# 2025_06_24_cam.net
KiCad netlist of a schematic drawn in EasyEDA Pro
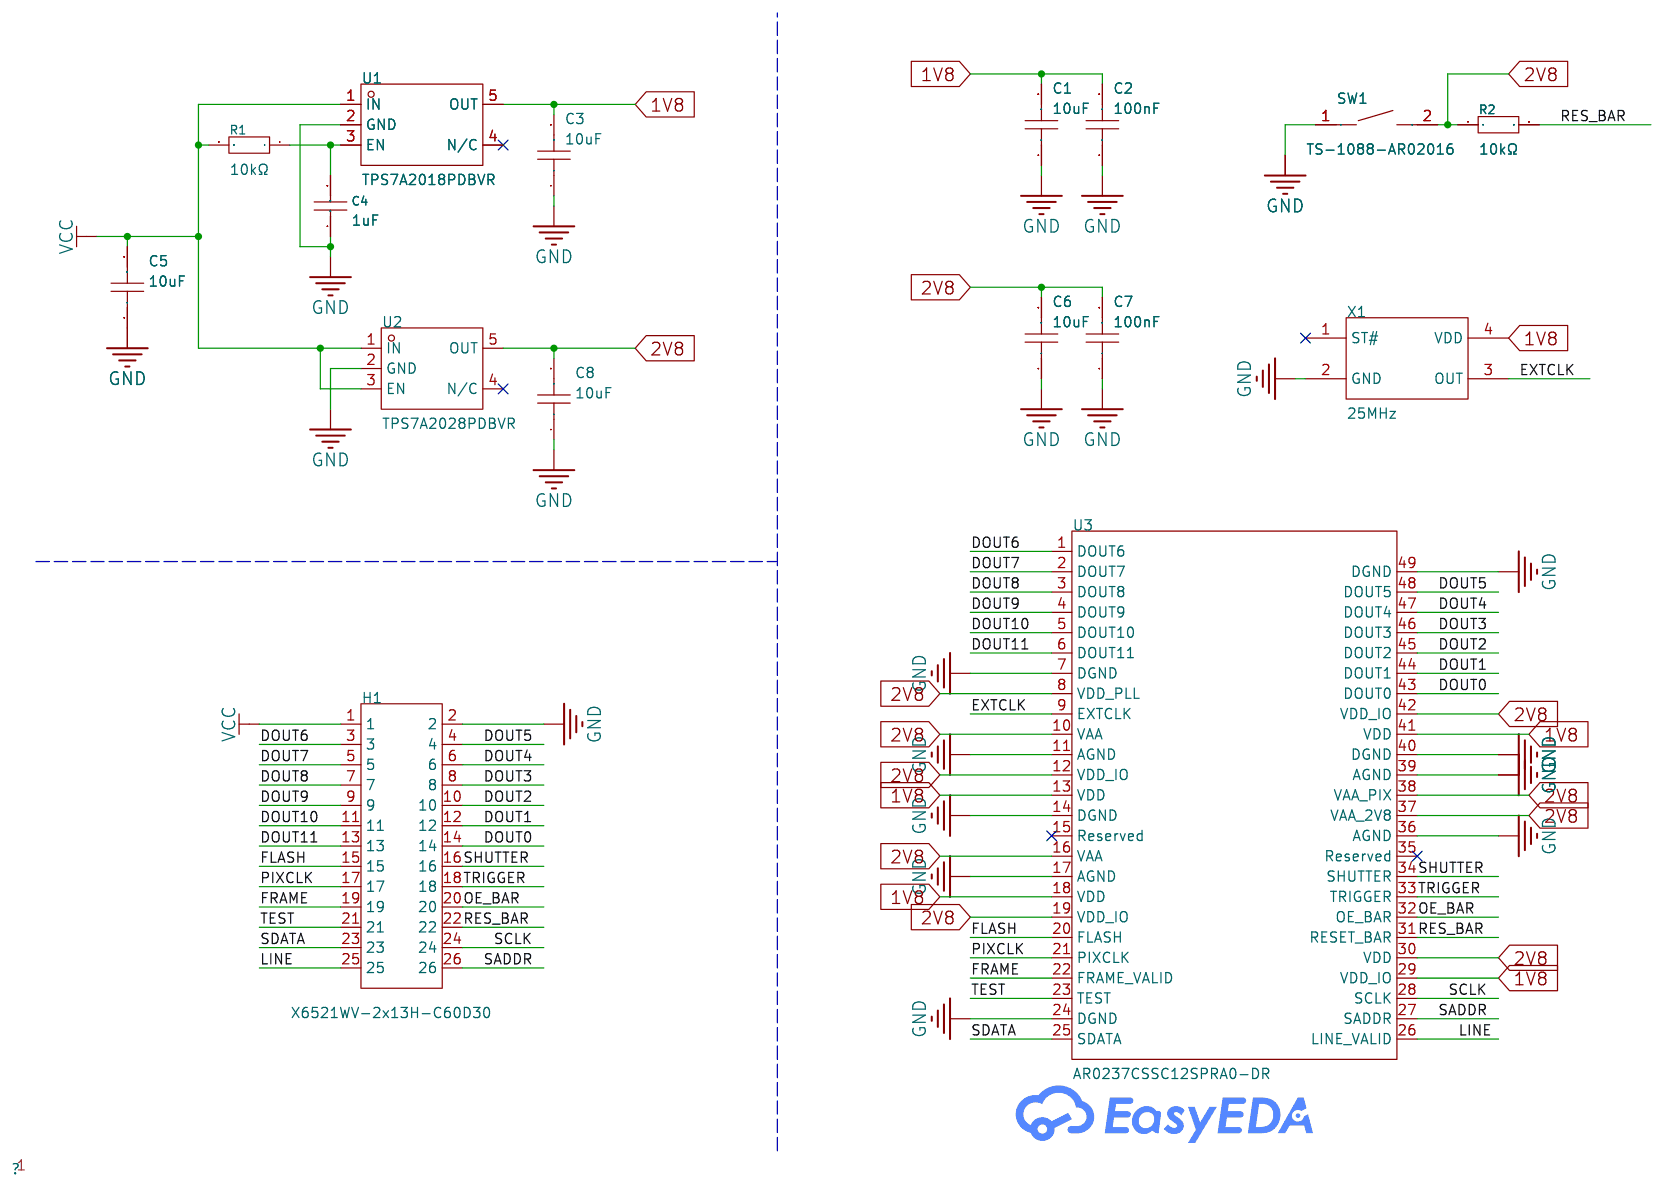
[diagram p0: schematic sheet]

(export (version "E")
  (design (tool "Eeschema 10.0.6"))
  (components
    (comp (ref "C1")
      (value "10uF")
      (footprint "easyedapro:C0402")
      (fields
        (field (name "Manufacturer Part") "CL05A106MP5NUNC")
        (field (name "Manufacturer") "SAMSUNG(三星)")
      )
      (libsource (lib "easyedapro") (part "CL05A106MP5NUNC_C315248"))
    )
    (comp (ref "C2")
      (value "100nF")
      (footprint "easyedapro:C0402")
      (fields
        (field (name "Manufacturer Part") "CL05B104KO5NNNC")
        (field (name "Manufacturer") "SAMSUNG(三星)")
      )
      (libsource (lib "easyedapro") (part "CL05B104KO5NNNC"))
    )
    (comp (ref "C3")
      (value "10uF")
      (footprint "easyedapro:C0402")
      (fields
        (field (name "Manufacturer Part") "CL05A106MP5NUNC")
        (field (name "Manufacturer") "SAMSUNG(三星)")
      )
      (libsource (lib "easyedapro") (part "CL05A106MP5NUNC_C315248"))
    )
    (comp (ref "C4")
      (value "1uF")
      (footprint "easyedapro:C0402")
      (fields
        (field (name "Manufacturer Part") "CL05A105KO5NNNC")
        (field (name "Manufacturer") "SAMSUNG(三星)")
      )
      (libsource (lib "easyedapro") (part "CL05A105KO5NNNC"))
    )
    (comp (ref "C5")
      (value "10uF")
      (footprint "easyedapro:C0402")
      (fields
        (field (name "Manufacturer Part") "CL05A106MP5NUNC")
        (field (name "Manufacturer") "SAMSUNG(三星)")
      )
      (libsource (lib "easyedapro") (part "CL05A106MP5NUNC_C315248"))
    )
    (comp (ref "C6")
      (value "10uF")
      (footprint "easyedapro:C0402")
      (fields
        (field (name "Manufacturer Part") "CL05A106MP5NUNC")
        (field (name "Manufacturer") "SAMSUNG(三星)")
      )
      (libsource (lib "easyedapro") (part "CL05A106MP5NUNC_C315248"))
    )
    (comp (ref "C7")
      (value "100nF")
      (footprint "easyedapro:C0402")
      (fields
        (field (name "Manufacturer Part") "CL05B104KO5NNNC")
        (field (name "Manufacturer") "SAMSUNG(三星)")
      )
      (libsource (lib "easyedapro") (part "CL05B104KO5NNNC"))
    )
    (comp (ref "C8")
      (value "10uF")
      (footprint "easyedapro:C0402")
      (fields
        (field (name "Manufacturer Part") "CL05A106MP5NUNC")
        (field (name "Manufacturer") "SAMSUNG(三星)")
      )
      (libsource (lib "easyedapro") (part "CL05A106MP5NUNC_C315248"))
    )
    (comp (ref "H1")
      (value "X6521WV-2x13H-C60D30")
      (footprint "easyedapro:HDR-TH_26P-P2.54-V-M-R2-C13-S2.54")
      (fields (field (name "Manufacturer") "XKB Connection(中国星坤)"))
      (libsource (lib "easyedapro") (part "X6521WV-2×13H-C30D60"))
    )
    (comp (ref "R1")
      (value "10kΩ")
      (footprint "easyedapro:R0402")
      (fields
        (field (name "Manufacturer Part") "0402WGJ0103TCE")
        (field (name "Manufacturer") "UNI-ROYAL(厚声)")
      )
      (libsource (lib "easyedapro") (part "0402WGJ0103TCE"))
    )
    (comp (ref "R2")
      (value "10kΩ")
      (footprint "easyedapro:R0402")
      (fields
        (field (name "Manufacturer Part") "0402WGJ0103TCE")
        (field (name "Manufacturer") "UNI-ROYAL(厚声)")
      )
      (libsource (lib "easyedapro") (part "0402WGJ0103TCE"))
    )
    (comp (ref "SW1")
      (value "TS-1088-AR02016")
      (footprint "easyedapro:SW-SMD_L3.9-W3.0-P4.45")
      (fields (field (name "Manufacturer") "XUNPU(讯普)"))
      (libsource (lib "easyedapro") (part "TS-1088-AR02016"))
    )
    (comp (ref "U1")
      (value "TPS7A2018PDBVR")
      (footprint "easyedapro:SOT-23-5_L2.9-W1.6-P0.95-LS2.8-BR")
      (fields (field (name "Manufacturer") "TI(德州仪器)"))
      (libsource (lib "easyedapro") (part "TPS7A2018PDBVR"))
    )
    (comp (ref "U2")
      (value "TPS7A2028PDBVR")
      (footprint "easyedapro:SOT-23-5_L2.9-W1.6-P0.95-LS2.8-BR")
      (fields (field (name "Manufacturer") "TI(德州仪器)"))
      (libsource (lib "easyedapro") (part "TPS7A2028PDBVR"))
    )
    (comp (ref "U3")
      (value "AR0237CSSC12SPRA0-DR")
      (footprint "easyedapro:MPLCC-48_L11.4-W11.4-P0.80-TL_AR0237CS")
      (fields (field (name "Manufacturer") "onsemi(安森美)"))
      (libsource (lib "easyedapro") (part "AR0237CSSC12SPRA0-DR"))
    )
    (comp (ref "X1")
      (value "25MHz")
      (footprint "easyedapro:OSC-SMD_4P-L2.5-W2.0-BL")
      (fields (field (name "Manufacturer Part") "X1G0041710033") (field (name "Manufacturer") "EPSON(爱普生)"))
      (libsource (lib "easyedapro") (part "X1G004171003300"))
    )
  )
  (nets
    (net (code "1") (name "/DOUT0") (class "Default")
      (node (ref "H1") (pin "14") (pinfunction "14_14") (pintype "unspecified"))
      (node (ref "U3") (pin "43") (pinfunction "DOUT0_43") (pintype "unspecified"))
    )
    (net (code "2") (name "/DOUT1") (class "Default")
      (node (ref "H1") (pin "12") (pinfunction "12_12") (pintype "unspecified"))
      (node (ref "U3") (pin "44") (pinfunction "DOUT1_44") (pintype "unspecified"))
    )
    (net (code "3") (name "/DOUT2") (class "Default")
      (node (ref "H1") (pin "10") (pinfunction "10_10") (pintype "unspecified"))
      (node (ref "U3") (pin "45") (pinfunction "DOUT2_45") (pintype "unspecified"))
    )
    (net (code "4") (name "/DOUT3") (class "Default")
      (node (ref "H1") (pin "8") (pinfunction "8_8") (pintype "unspecified"))
      (node (ref "U3") (pin "46") (pinfunction "DOUT3_46") (pintype "unspecified"))
    )
    (net (code "5") (name "/DOUT4") (class "Default")
      (node (ref "H1") (pin "6") (pinfunction "6_6") (pintype "unspecified"))
      (node (ref "U3") (pin "47") (pinfunction "DOUT4_47") (pintype "unspecified"))
    )
    (net (code "6") (name "/DOUT5") (class "Default")
      (node (ref "H1") (pin "4") (pinfunction "4_4") (pintype "unspecified"))
      (node (ref "U3") (pin "48") (pinfunction "DOUT5_48") (pintype "unspecified"))
    )
    (net (code "7") (name "/DOUT6") (class "Default")
      (node (ref "H1") (pin "3") (pinfunction "3_3") (pintype "unspecified"))
      (node (ref "U3") (pin "1") (pinfunction "DOUT6_1") (pintype "unspecified"))
    )
    (net (code "8") (name "/DOUT7") (class "Default")
      (node (ref "H1") (pin "5") (pinfunction "5_5") (pintype "unspecified"))
      (node (ref "U3") (pin "2") (pinfunction "DOUT7_2") (pintype "unspecified"))
    )
    (net (code "9") (name "/DOUT8") (class "Default")
      (node (ref "H1") (pin "7") (pinfunction "7_7") (pintype "unspecified"))
      (node (ref "U3") (pin "3") (pinfunction "DOUT8_3") (pintype "unspecified"))
    )
    (net (code "10") (name "/DOUT9") (class "Default")
      (node (ref "H1") (pin "9") (pinfunction "9_9") (pintype "unspecified"))
      (node (ref "U3") (pin "4") (pinfunction "DOUT9_4") (pintype "unspecified"))
    )
    (net (code "11") (name "/DOUT10") (class "Default")
      (node (ref "H1") (pin "11") (pinfunction "11_11") (pintype "unspecified"))
      (node (ref "U3") (pin "5") (pinfunction "DOUT10_5") (pintype "unspecified"))
    )
    (net (code "12") (name "/DOUT11") (class "Default")
      (node (ref "H1") (pin "13") (pinfunction "13_13") (pintype "unspecified"))
      (node (ref "U3") (pin "6") (pinfunction "DOUT11_6") (pintype "unspecified"))
    )
    (net (code "13") (name "/EXTCLK") (class "Default")
      (node (ref "U3") (pin "9") (pinfunction "EXTCLK_9") (pintype "unspecified"))
      (node (ref "X1") (pin "3") (pinfunction "OUT_3") (pintype "unspecified"))
    )
    (net (code "14") (name "/FLASH") (class "Default")
      (node (ref "H1") (pin "15") (pinfunction "15_15") (pintype "unspecified"))
      (node (ref "U3") (pin "20") (pinfunction "FLASH_20") (pintype "unspecified"))
    )
    (net (code "15") (name "/FRAME") (class "Default")
      (node (ref "H1") (pin "19") (pinfunction "19_19") (pintype "unspecified"))
      (node (ref "U3") (pin "22") (pinfunction "FRAME_VALID_22") (pintype "unspecified"))
    )
    (net (code "16") (name "/LINE") (class "Default")
      (node (ref "H1") (pin "25") (pinfunction "25_25") (pintype "unspecified"))
      (node (ref "U3") (pin "26") (pinfunction "LINE_VALID_26") (pintype "unspecified"))
    )
    (net (code "17") (name "/OE_BAR") (class "Default")
      (node (ref "H1") (pin "20") (pinfunction "20_20") (pintype "unspecified"))
      (node (ref "U3") (pin "32") (pinfunction "OE_BAR_32") (pintype "unspecified"))
    )
    (net (code "18") (name "/PIXCLK") (class "Default")
      (node (ref "H1") (pin "17") (pinfunction "17_17") (pintype "unspecified"))
      (node (ref "U3") (pin "21") (pinfunction "PIXCLK_21") (pintype "unspecified"))
    )
    (net (code "19") (name "/RES_BAR") (class "Default")
      (node (ref "H1") (pin "22") (pinfunction "22_22") (pintype "unspecified"))
      (node (ref "R2") (pin "2") (pinfunction "2_2") (pintype "input"))
      (node (ref "U3") (pin "31") (pinfunction "RESET_BAR_31") (pintype "unspecified"))
    )
    (net (code "20") (name "/SADDR") (class "Default")
      (node (ref "H1") (pin "26") (pinfunction "26_26") (pintype "unspecified"))
      (node (ref "U3") (pin "27") (pinfunction "SADDR_27") (pintype "unspecified"))
    )
    (net (code "21") (name "/SCLK") (class "Default")
      (node (ref "H1") (pin "24") (pinfunction "24_24") (pintype "unspecified"))
      (node (ref "U3") (pin "28") (pinfunction "SCLK_28") (pintype "unspecified"))
    )
    (net (code "22") (name "/SDATA") (class "Default")
      (node (ref "H1") (pin "23") (pinfunction "23_23") (pintype "unspecified"))
      (node (ref "U3") (pin "25") (pinfunction "SDATA_25") (pintype "unspecified"))
    )
    (net (code "23") (name "/SHUTTER") (class "Default")
      (node (ref "H1") (pin "16") (pinfunction "16_16") (pintype "unspecified"))
      (node (ref "U3") (pin "34") (pinfunction "SHUTTER_34") (pintype "unspecified"))
    )
    (net (code "24") (name "/TEST") (class "Default")
      (node (ref "H1") (pin "21") (pinfunction "21_21") (pintype "unspecified"))
      (node (ref "U3") (pin "23") (pinfunction "TEST_23") (pintype "unspecified"))
    )
    (net (code "25") (name "/TRIGGER") (class "Default")
      (node (ref "H1") (pin "18") (pinfunction "18_18") (pintype "unspecified"))
      (node (ref "U3") (pin "33") (pinfunction "TRIGGER_33") (pintype "unspecified"))
    )
    (net (code "26") (name "1V8") (class "Default")
      (node (ref "C1") (pin "2") (pinfunction "2_2") (pintype "unspecified"))
      (node (ref "C2") (pin "2") (pinfunction "2_2") (pintype "unspecified"))
      (node (ref "C3") (pin "2") (pinfunction "2_2") (pintype "unspecified"))
      (node (ref "U1") (pin "5") (pinfunction "OUT_5") (pintype "unspecified"))
      (node (ref "U3") (pin "13") (pinfunction "VDD_13") (pintype "unspecified"))
      (node (ref "U3") (pin "18") (pinfunction "VDD_18") (pintype "unspecified"))
      (node (ref "U3") (pin "29") (pinfunction "VDD_IO_29") (pintype "unspecified"))
      (node (ref "U3") (pin "41") (pinfunction "VDD_41") (pintype "unspecified"))
      (node (ref "X1") (pin "4") (pinfunction "VDD_4") (pintype "unspecified"))
    )
    (net (code "27") (name "2V8") (class "Default")
      (node (ref "C6") (pin "2") (pinfunction "2_2") (pintype "unspecified"))
      (node (ref "C7") (pin "2") (pinfunction "2_2") (pintype "unspecified"))
      (node (ref "C8") (pin "2") (pinfunction "2_2") (pintype "unspecified"))
      (node (ref "R2") (pin "1") (pinfunction "1_1") (pintype "input"))
      (node (ref "SW1") (pin "2") (pinfunction "2_2") (pintype "unspecified"))
      (node (ref "U2") (pin "5") (pinfunction "OUT_5") (pintype "unspecified"))
      (node (ref "U3") (pin "10") (pinfunction "VAA_10") (pintype "unspecified"))
      (node (ref "U3") (pin "12") (pinfunction "VDD_IO_12") (pintype "unspecified"))
      (node (ref "U3") (pin "16") (pinfunction "VAA_16") (pintype "unspecified"))
      (node (ref "U3") (pin "19") (pinfunction "VDD_IO_19") (pintype "unspecified"))
      (node (ref "U3") (pin "30") (pinfunction "VDD_30") (pintype "unspecified"))
      (node (ref "U3") (pin "37") (pinfunction "VAA_2V8_37") (pintype "unspecified"))
      (node (ref "U3") (pin "38") (pinfunction "VAA_PIX_38") (pintype "unspecified"))
      (node (ref "U3") (pin "42") (pinfunction "VDD_IO_42") (pintype "unspecified"))
      (node (ref "U3") (pin "8") (pinfunction "VDD_PLL_8") (pintype "unspecified"))
    )
    (net (code "28") (name "GND") (class "Default")
      (node (ref "C1") (pin "1") (pinfunction "1_1") (pintype "unspecified"))
      (node (ref "C2") (pin "1") (pinfunction "1_1") (pintype "unspecified"))
      (node (ref "C3") (pin "1") (pinfunction "1_1") (pintype "unspecified"))
      (node (ref "C4") (pin "1") (pinfunction "1_1") (pintype "input"))
      (node (ref "C5") (pin "1") (pinfunction "1_1") (pintype "unspecified"))
      (node (ref "C6") (pin "1") (pinfunction "1_1") (pintype "unspecified"))
      (node (ref "C7") (pin "1") (pinfunction "1_1") (pintype "unspecified"))
      (node (ref "C8") (pin "1") (pinfunction "1_1") (pintype "unspecified"))
      (node (ref "H1") (pin "2") (pinfunction "2_2") (pintype "unspecified"))
      (node (ref "SW1") (pin "1") (pinfunction "1_1") (pintype "unspecified"))
      (node (ref "U1") (pin "2") (pinfunction "GND_2") (pintype "unspecified"))
      (node (ref "U2") (pin "2") (pinfunction "GND_2") (pintype "unspecified"))
      (node (ref "U3") (pin "11") (pinfunction "AGND_11") (pintype "unspecified"))
      (node (ref "U3") (pin "14") (pinfunction "DGND_14") (pintype "unspecified"))
      (node (ref "U3") (pin "17") (pinfunction "AGND_17") (pintype "unspecified"))
      (node (ref "U3") (pin "24") (pinfunction "DGND_24") (pintype "unspecified"))
      (node (ref "U3") (pin "36") (pinfunction "AGND_36") (pintype "unspecified"))
      (node (ref "U3") (pin "39") (pinfunction "AGND_39") (pintype "unspecified"))
      (node (ref "U3") (pin "40") (pinfunction "DGND_40") (pintype "unspecified"))
      (node (ref "U3") (pin "49") (pinfunction "DGND_49") (pintype "unspecified"))
      (node (ref "U3") (pin "7") (pinfunction "DGND_7") (pintype "unspecified"))
      (node (ref "X1") (pin "2") (pinfunction "GND_2") (pintype "unspecified"))
    )
    (net (code "29") (name "Net-(U1-EN)") (class "Default")
      (node (ref "C4") (pin "2") (pinfunction "2_2") (pintype "input"))
      (node (ref "R1") (pin "1") (pinfunction "1_1") (pintype "input"))
      (node (ref "U1") (pin "3") (pinfunction "EN_3") (pintype "unspecified"))
    )
    (net (code "30") (name "VCC") (class "Default")
      (node (ref "C5") (pin "2") (pinfunction "2_2") (pintype "unspecified"))
      (node (ref "H1") (pin "1") (pinfunction "1_1") (pintype "unspecified"))
      (node (ref "R1") (pin "2") (pinfunction "2_2") (pintype "input"))
      (node (ref "U1") (pin "1") (pinfunction "IN_1") (pintype "unspecified"))
      (node (ref "U2") (pin "1") (pinfunction "IN_1") (pintype "unspecified"))
      (node (ref "U2") (pin "3") (pinfunction "EN_3") (pintype "unspecified"))
    )
    (net (code "31") (name "unconnected-(U1-N{slash}C-Pad4)") (class "Default")
      (node (ref "U1") (pin "4") (pinfunction "N/C_4") (pintype "unspecified+no_connect"))
    )
    (net (code "32") (name "unconnected-(U2-N{slash}C-Pad4)") (class "Default")
      (node (ref "U2") (pin "4") (pinfunction "N/C_4") (pintype "unspecified+no_connect"))
    )
    (net (code "33") (name "unconnected-(U3-Reserved-Pad15)") (class "Default")
      (node (ref "U3") (pin "15") (pinfunction "Reserved_15") (pintype "unspecified+no_connect"))
    )
    (net (code "34") (name "unconnected-(U3-Reserved-Pad35)") (class "Default")
      (node (ref "U3") (pin "35") (pinfunction "Reserved_35") (pintype "unspecified+no_connect"))
    )
    (net (code "35") (name "unconnected-(X1-ST#-Pad1)") (class "Default")
      (node (ref "X1") (pin "1") (pinfunction "ST#_1") (pintype "unspecified+no_connect"))
    )
  )
)
